# InternetButtonBuzzer.net
KiCad netlist of a schematic drawn in EAGLE
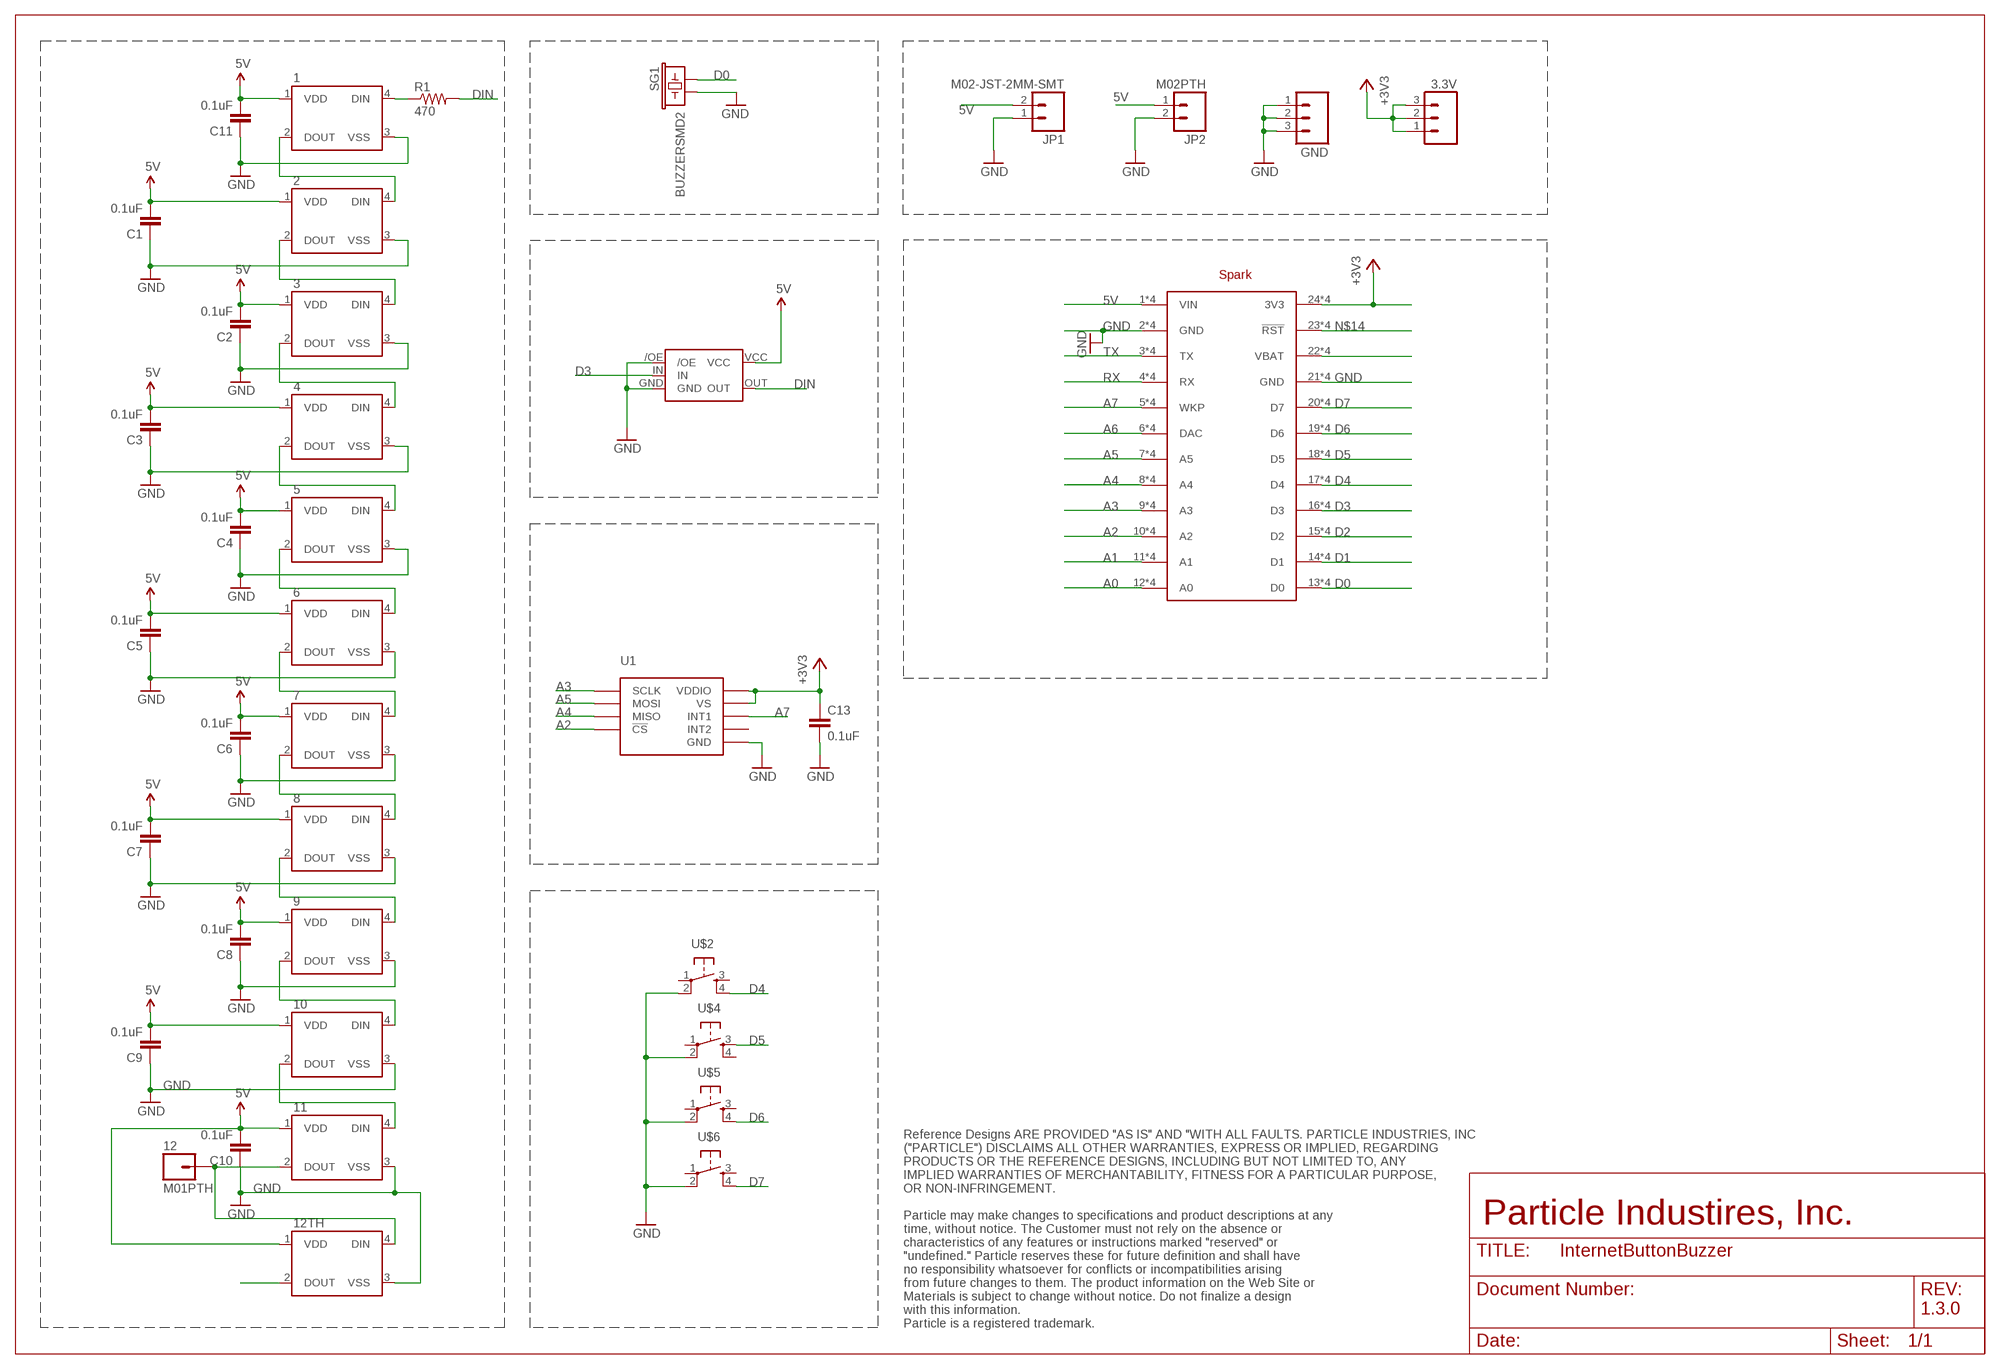
[diagram p0: schematic, sheet 1]

(export (version "E")
  (design (tool "Eeschema 10.0.6"))
  (components
    (comp (ref "1")
      (value "WS2812B")
      (footprint "eagle-import:WS2812B")
      (libsource (lib "eagle-import") (part "SparkFun-LED_WS2812B"))
    )
    (comp (ref "2")
      (value "WS2812B")
      (footprint "eagle-import:WS2812B")
      (libsource (lib "eagle-import") (part "SparkFun-LED_WS2812B"))
    )
    (comp (ref "3")
      (value "WS2812B")
      (footprint "eagle-import:WS2812B")
      (libsource (lib "eagle-import") (part "SparkFun-LED_WS2812B"))
    )
    (comp (ref "3.3V")
      (value "M03LOCK_NO_SILK")
      (footprint "eagle-import:1X03_LOCK_NO_SILK")
      (libsource (lib "eagle-import") (part "M03LOCK_NO_SILK"))
    )
    (comp (ref "4")
      (value "WS2812B")
      (footprint "eagle-import:WS2812B")
      (libsource (lib "eagle-import") (part "SparkFun-LED_WS2812B"))
    )
    (comp (ref "5")
      (value "WS2812B")
      (footprint "eagle-import:WS2812B")
      (libsource (lib "eagle-import") (part "SparkFun-LED_WS2812B"))
    )
    (comp (ref "6")
      (value "WS2812B")
      (footprint "eagle-import:WS2812B")
      (libsource (lib "eagle-import") (part "SparkFun-LED_WS2812B"))
    )
    (comp (ref "7")
      (value "WS2812B")
      (footprint "eagle-import:WS2812B")
      (libsource (lib "eagle-import") (part "SparkFun-LED_WS2812B"))
    )
    (comp (ref "8")
      (value "WS2812B")
      (footprint "eagle-import:WS2812B")
      (libsource (lib "eagle-import") (part "SparkFun-LED_WS2812B"))
    )
    (comp (ref "9")
      (value "WS2812B")
      (footprint "eagle-import:WS2812B")
      (libsource (lib "eagle-import") (part "SparkFun-LED_WS2812B"))
    )
    (comp (ref "10")
      (value "WS2812B")
      (footprint "eagle-import:WS2812B")
      (libsource (lib "eagle-import") (part "SparkFun-LED_WS2812B"))
    )
    (comp (ref "11")
      (value "WS2812B")
      (footprint "eagle-import:WS2812B")
      (libsource (lib "eagle-import") (part "SparkFun-LED_WS2812B"))
    )
    (comp (ref "12")
      (value "M01PTH")
      (footprint "eagle-import:1X01")
      (libsource (lib "eagle-import") (part "M01PTH"))
    )
    (comp (ref "12TH")
      (value "WS2812B")
      (footprint "eagle-import:NOCREAM_WS2812B")
      (libsource (lib "eagle-import") (part "WS2812B"))
    )
    (comp (ref "C1")
      (value "0.1uF")
      (footprint "eagle-import:0603-CAP")
      (libsource (lib "eagle-import") (part "15PF-50V-5%(0603)"))
    )
    (comp (ref "C2")
      (value "0.1uF")
      (footprint "eagle-import:0603-CAP")
      (libsource (lib "eagle-import") (part "15PF-50V-5%(0603)"))
    )
    (comp (ref "C3")
      (value "0.1uF")
      (footprint "eagle-import:0603-CAP")
      (libsource (lib "eagle-import") (part "15PF-50V-5%(0603)"))
    )
    (comp (ref "C4")
      (value "0.1uF")
      (footprint "eagle-import:0603-CAP")
      (libsource (lib "eagle-import") (part "15PF-50V-5%(0603)"))
    )
    (comp (ref "C5")
      (value "0.1uF")
      (footprint "eagle-import:0603-CAP")
      (libsource (lib "eagle-import") (part "15PF-50V-5%(0603)"))
    )
    (comp (ref "C6")
      (value "0.1uF")
      (footprint "eagle-import:0603-CAP")
      (libsource (lib "eagle-import") (part "15PF-50V-5%(0603)"))
    )
    (comp (ref "C7")
      (value "0.1uF")
      (footprint "eagle-import:0603-CAP")
      (libsource (lib "eagle-import") (part "15PF-50V-5%(0603)"))
    )
    (comp (ref "C8")
      (value "0.1uF")
      (footprint "eagle-import:0603-CAP")
      (libsource (lib "eagle-import") (part "15PF-50V-5%(0603)"))
    )
    (comp (ref "C9")
      (value "0.1uF")
      (footprint "eagle-import:0603-CAP")
      (libsource (lib "eagle-import") (part "15PF-50V-5%(0603)"))
    )
    (comp (ref "C10")
      (value "0.1uF")
      (footprint "eagle-import:0603-CAP")
      (libsource (lib "eagle-import") (part "15PF-50V-5%(0603)"))
    )
    (comp (ref "C11")
      (value "0.1uF")
      (footprint "eagle-import:0603-CAP")
      (libsource (lib "eagle-import") (part "15PF-50V-5%(0603)"))
    )
    (comp (ref "C13")
      (value "0.1uF")
      (footprint "eagle-import:0603-CAP")
      (libsource (lib "eagle-import") (part "CAP0603-CAP"))
    )
    (comp (ref "GND")
      (value "M03LOCK_NO_SILK")
      (footprint "eagle-import:1X03_LOCK_NO_SILK")
      (libsource (lib "eagle-import") (part "M03LOCK_NO_SILK"))
    )
    (comp (ref "JP1")
      (value "M02-JST-2MM-SMT")
      (footprint "eagle-import:JST-2-SMD")
      (libsource (lib "eagle-import") (part "M02-JST-2MM-SMT"))
    )
    (comp (ref "JP2")
      (value "M02PTH")
      (footprint "eagle-import:1X02")
      (libsource (lib "eagle-import") (part "M02PTH"))
    )
    (comp (ref "R1")
      (value "470")
      (footprint "eagle-import:0603-RES")
      (libsource (lib "eagle-import") (part "470OHM1/10W1%(0603)"))
    )
    (comp (ref "SG1")
      (value "BUZZERSMD2")
      (footprint "eagle-import:BUZZER-CCV")
      (libsource (lib "eagle-import") (part "BUZZERSMD2"))
    )
    (comp (ref "U$2")
      (value "12MM_TACTILE_SWITCH")
      (footprint "eagle-import:12MM_TACTILE_SWITCH")
      (libsource (lib "eagle-import") (part "12MM_TACTILE_SWITCH"))
    )
    (comp (ref "U$3")
      (value "SPARK_LOGO_WITH_PLANE")
      (footprint "eagle-import:SPARK_LOGO_PLUS_PLANE")
      (libsource (lib "eagle-import") (part "SPARK_LOGO_WITH_PLANE"))
    )
    (comp (ref "U$4")
      (value "12MM_TACTILE_SWITCH")
      (footprint "eagle-import:12MM_TACTILE_SWITCH")
      (libsource (lib "eagle-import") (part "12MM_TACTILE_SWITCH"))
    )
    (comp (ref "U$5")
      (value "12MM_TACTILE_SWITCH")
      (footprint "eagle-import:12MM_TACTILE_SWITCH")
      (libsource (lib "eagle-import") (part "12MM_TACTILE_SWITCH"))
    )
    (comp (ref "U$6")
      (value "12MM_TACTILE_SWITCH")
      (footprint "eagle-import:12MM_TACTILE_SWITCH")
      (libsource (lib "eagle-import") (part "12MM_TACTILE_SWITCH"))
    )
    (comp (ref "U$7")
      (value "SPARK_COREDUAL_HEADER")
      (footprint "eagle-import:SPARK_CORE_DUAL_HEADER")
      (libsource (lib "eagle-import") (part "SPARK_COREDUAL_HEADER"))
    )
    (comp (ref "U$8")
      (value "NL17SZ125SOT553")
      (footprint "eagle-import:SOT-553")
      (libsource (lib "eagle-import") (part "NL17SZ125SOT553"))
    )
    (comp (ref "U1")
      (value "ADXL362ADXL362-1:1")
      (footprint "eagle-import:ADXL362-1_1")
      (libsource (lib "eagle-import") (part "ADXL362ADXL362-1{colon}1"))
    )
  )
  (nets
    (net (code "1") (name "+3V3") (class "Default")
      (node (ref "3.3V") (pin "1") (pinfunction "1_1") (pintype "passive"))
      (node (ref "3.3V") (pin "2") (pinfunction "2_2") (pintype "passive"))
      (node (ref "3.3V") (pin "3") (pinfunction "3_3") (pintype "passive"))
      (node (ref "C13") (pin "1") (pinfunction "1_1") (pintype "passive"))
      (node (ref "U$7") (pin "24") (pinfunction "3V3_24") (pintype "power_in"))
      (node (ref "U$7") (pin "24B") (pinfunction "3V3_24B") (pintype "power_in"))
      (node (ref "U$7") (pin "@24") (pinfunction "3V3_@24") (pintype "power_in"))
      (node (ref "U$7") (pin "@24B") (pinfunction "3V3_@24B") (pintype "power_in"))
      (node (ref "U1") (pin "P$1") (pinfunction "VDDIO_P$1") (pintype "bidirectional"))
      (node (ref "U1") (pin "P$14") (pinfunction "VS_P$14") (pintype "bidirectional"))
    )
    (net (code "2") (name "/A0") (class "Default")
      (node (ref "U$7") (pin "12") (pinfunction "A0_12") (pintype "bidirectional"))
      (node (ref "U$7") (pin "12B") (pinfunction "A0_12B") (pintype "bidirectional"))
      (node (ref "U$7") (pin "@12") (pinfunction "A0_@12") (pintype "bidirectional"))
      (node (ref "U$7") (pin "@12B") (pinfunction "A0_@12B") (pintype "bidirectional"))
    )
    (net (code "3") (name "/A1") (class "Default")
      (node (ref "U$7") (pin "11") (pinfunction "A1_11") (pintype "bidirectional"))
      (node (ref "U$7") (pin "11B") (pinfunction "A1_11B") (pintype "bidirectional"))
      (node (ref "U$7") (pin "@11") (pinfunction "A1_@11") (pintype "bidirectional"))
      (node (ref "U$7") (pin "@11B") (pinfunction "A1_@11B") (pintype "bidirectional"))
    )
    (net (code "4") (name "/A2") (class "Default")
      (node (ref "U$7") (pin "10") (pinfunction "A2_10") (pintype "bidirectional"))
      (node (ref "U$7") (pin "10B") (pinfunction "A2_10B") (pintype "bidirectional"))
      (node (ref "U$7") (pin "@10") (pinfunction "A2_@10") (pintype "bidirectional"))
      (node (ref "U$7") (pin "@10B") (pinfunction "A2_@10B") (pintype "bidirectional"))
      (node (ref "U1") (pin "P$8") (pinfunction "~{CS}_P$8") (pintype "bidirectional"))
    )
    (net (code "5") (name "/A3") (class "Default")
      (node (ref "U$7") (pin "9") (pinfunction "A3_9") (pintype "bidirectional"))
      (node (ref "U$7") (pin "9B") (pinfunction "A3_9B") (pintype "bidirectional"))
      (node (ref "U$7") (pin "@9") (pinfunction "A3_@9") (pintype "bidirectional"))
      (node (ref "U$7") (pin "@9B") (pinfunction "A3_@9B") (pintype "bidirectional"))
      (node (ref "U1") (pin "P$4") (pinfunction "SCLK_P$4") (pintype "bidirectional"))
    )
    (net (code "6") (name "/A4") (class "Default")
      (node (ref "U$7") (pin "8") (pinfunction "A4_8") (pintype "bidirectional"))
      (node (ref "U$7") (pin "8B") (pinfunction "A4_8B") (pintype "bidirectional"))
      (node (ref "U$7") (pin "@8") (pinfunction "A4_@8") (pintype "bidirectional"))
      (node (ref "U$7") (pin "@8B") (pinfunction "A4_@8B") (pintype "bidirectional"))
      (node (ref "U1") (pin "P$7") (pinfunction "MISO_P$7") (pintype "bidirectional"))
    )
    (net (code "7") (name "/A5") (class "Default")
      (node (ref "U$7") (pin "7") (pinfunction "A5_7") (pintype "bidirectional"))
      (node (ref "U$7") (pin "7B") (pinfunction "A5_7B") (pintype "bidirectional"))
      (node (ref "U$7") (pin "@7") (pinfunction "A5_@7") (pintype "bidirectional"))
      (node (ref "U$7") (pin "@7B") (pinfunction "A5_@7B") (pintype "bidirectional"))
      (node (ref "U1") (pin "P$6") (pinfunction "MOSI_P$6") (pintype "bidirectional"))
    )
    (net (code "8") (name "/A6") (class "Default")
      (node (ref "U$7") (pin "6") (pinfunction "DAC_6") (pintype "bidirectional"))
      (node (ref "U$7") (pin "6B") (pinfunction "DAC_6B") (pintype "bidirectional"))
      (node (ref "U$7") (pin "@6") (pinfunction "DAC_@6") (pintype "bidirectional"))
      (node (ref "U$7") (pin "@6B") (pinfunction "DAC_@6B") (pintype "bidirectional"))
    )
    (net (code "9") (name "/A7") (class "Default")
      (node (ref "U$7") (pin "5") (pinfunction "WKP_5") (pintype "bidirectional"))
      (node (ref "U$7") (pin "5B") (pinfunction "WKP_5B") (pintype "bidirectional"))
      (node (ref "U$7") (pin "@5") (pinfunction "WKP_@5") (pintype "bidirectional"))
      (node (ref "U$7") (pin "@5B") (pinfunction "WKP_@5B") (pintype "bidirectional"))
      (node (ref "U1") (pin "P$11") (pinfunction "INT1_P$11") (pintype "bidirectional"))
    )
    (net (code "10") (name "/D0") (class "Default")
      (node (ref "SG1") (pin "+") (pinfunction "1_+") (pintype "passive"))
      (node (ref "U$7") (pin "13") (pinfunction "D0_13") (pintype "bidirectional"))
      (node (ref "U$7") (pin "13B") (pinfunction "D0_13B") (pintype "bidirectional"))
      (node (ref "U$7") (pin "@13") (pinfunction "D0_@13") (pintype "bidirectional"))
      (node (ref "U$7") (pin "@13B") (pinfunction "D0_@13B") (pintype "bidirectional"))
    )
    (net (code "11") (name "/D1") (class "Default")
      (node (ref "U$7") (pin "14") (pinfunction "D1_14") (pintype "bidirectional"))
      (node (ref "U$7") (pin "14B") (pinfunction "D1_14B") (pintype "bidirectional"))
      (node (ref "U$7") (pin "@14") (pinfunction "D1_@14") (pintype "bidirectional"))
      (node (ref "U$7") (pin "@14B") (pinfunction "D1_@14B") (pintype "bidirectional"))
    )
    (net (code "12") (name "/D2") (class "Default")
      (node (ref "U$7") (pin "15") (pinfunction "D2_15") (pintype "bidirectional"))
      (node (ref "U$7") (pin "15B") (pinfunction "D2_15B") (pintype "bidirectional"))
      (node (ref "U$7") (pin "@15") (pinfunction "D2_@15") (pintype "bidirectional"))
      (node (ref "U$7") (pin "@15B") (pinfunction "D2_@15B") (pintype "bidirectional"))
    )
    (net (code "13") (name "/D3") (class "Default")
      (node (ref "U$7") (pin "16") (pinfunction "D3_16") (pintype "bidirectional"))
      (node (ref "U$7") (pin "16B") (pinfunction "D3_16B") (pintype "bidirectional"))
      (node (ref "U$7") (pin "@16") (pinfunction "D3_@16") (pintype "bidirectional"))
      (node (ref "U$7") (pin "@16B") (pinfunction "D3_@16B") (pintype "bidirectional"))
      (node (ref "U$8") (pin "IN") (pinfunction "IN_IN") (pintype "bidirectional"))
    )
    (net (code "14") (name "/D4") (class "Default")
      (node (ref "U$2") (pin "4") (pinfunction "4_4") (pintype "passive"))
      (node (ref "U$7") (pin "17") (pinfunction "D4_17") (pintype "bidirectional"))
      (node (ref "U$7") (pin "17B") (pinfunction "D4_17B") (pintype "bidirectional"))
      (node (ref "U$7") (pin "@17") (pinfunction "D4_@17") (pintype "bidirectional"))
      (node (ref "U$7") (pin "@17B") (pinfunction "D4_@17B") (pintype "bidirectional"))
    )
    (net (code "15") (name "/D5") (class "Default")
      (node (ref "U$4") (pin "3") (pinfunction "3_3") (pintype "passive"))
      (node (ref "U$7") (pin "18") (pinfunction "D5_18") (pintype "bidirectional"))
      (node (ref "U$7") (pin "18B") (pinfunction "D5_18B") (pintype "bidirectional"))
      (node (ref "U$7") (pin "@18") (pinfunction "D5_@18") (pintype "bidirectional"))
      (node (ref "U$7") (pin "@18B") (pinfunction "D5_@18B") (pintype "bidirectional"))
    )
    (net (code "16") (name "/D6") (class "Default")
      (node (ref "U$5") (pin "4") (pinfunction "4_4") (pintype "passive"))
      (node (ref "U$7") (pin "19") (pinfunction "D6_19") (pintype "bidirectional"))
      (node (ref "U$7") (pin "19B") (pinfunction "D6_19B") (pintype "bidirectional"))
      (node (ref "U$7") (pin "@19") (pinfunction "D6_@19") (pintype "bidirectional"))
      (node (ref "U$7") (pin "@19B") (pinfunction "D6_@19B") (pintype "bidirectional"))
    )
    (net (code "17") (name "/D7") (class "Default")
      (node (ref "U$6") (pin "4") (pinfunction "4_4") (pintype "passive"))
      (node (ref "U$7") (pin "20") (pinfunction "D7_20") (pintype "bidirectional"))
      (node (ref "U$7") (pin "20B") (pinfunction "D7_20B") (pintype "bidirectional"))
      (node (ref "U$7") (pin "@20") (pinfunction "D7_@20") (pintype "bidirectional"))
      (node (ref "U$7") (pin "@20B") (pinfunction "D7_@20B") (pintype "bidirectional"))
    )
    (net (code "18") (name "/DIN") (class "Default")
      (node (ref "R1") (pin "2") (pinfunction "2_2") (pintype "passive"))
      (node (ref "U$8") (pin "OUT") (pinfunction "OUT_OUT") (pintype "bidirectional"))
    )
    (net (code "19") (name "/N$14") (class "Default")
      (node (ref "U$7") (pin "23") (pinfunction "~{RST}_23") (pintype "bidirectional"))
      (node (ref "U$7") (pin "23B") (pinfunction "~{RST}_23B") (pintype "bidirectional"))
      (node (ref "U$7") (pin "@23") (pinfunction "~{RST}_@23") (pintype "bidirectional"))
      (node (ref "U$7") (pin "@23B") (pinfunction "~{RST}_@23B") (pintype "bidirectional"))
    )
    (net (code "20") (name "/RX") (class "Default")
      (node (ref "U$7") (pin "4") (pinfunction "RX_4") (pintype "bidirectional"))
      (node (ref "U$7") (pin "4B") (pinfunction "RX_4B") (pintype "bidirectional"))
      (node (ref "U$7") (pin "@4") (pinfunction "RX_@4") (pintype "bidirectional"))
      (node (ref "U$7") (pin "@4B") (pinfunction "RX_@4B") (pintype "bidirectional"))
    )
    (net (code "21") (name "/TX") (class "Default")
      (node (ref "U$7") (pin "3") (pinfunction "TX_3") (pintype "bidirectional"))
      (node (ref "U$7") (pin "3B") (pinfunction "TX_3B") (pintype "bidirectional"))
      (node (ref "U$7") (pin "@3") (pinfunction "TX_@3") (pintype "bidirectional"))
      (node (ref "U$7") (pin "@3B") (pinfunction "TX_@3B") (pintype "bidirectional"))
    )
    (net (code "22") (name "5V") (class "Default")
      (node (ref "1") (pin "1") (pinfunction "VDD_1") (pintype "power_in"))
      (node (ref "10") (pin "1") (pinfunction "VDD_1") (pintype "power_in"))
      (node (ref "11") (pin "1") (pinfunction "VDD_1") (pintype "power_in"))
      (node (ref "12TH") (pin "1") (pinfunction "VDD_1") (pintype "power_in"))
      (node (ref "2") (pin "1") (pinfunction "VDD_1") (pintype "power_in"))
      (node (ref "3") (pin "1") (pinfunction "VDD_1") (pintype "power_in"))
      (node (ref "4") (pin "1") (pinfunction "VDD_1") (pintype "power_in"))
      (node (ref "5") (pin "1") (pinfunction "VDD_1") (pintype "power_in"))
      (node (ref "6") (pin "1") (pinfunction "VDD_1") (pintype "power_in"))
      (node (ref "7") (pin "1") (pinfunction "VDD_1") (pintype "power_in"))
      (node (ref "8") (pin "1") (pinfunction "VDD_1") (pintype "power_in"))
      (node (ref "9") (pin "1") (pinfunction "VDD_1") (pintype "power_in"))
      (node (ref "C1") (pin "2") (pinfunction "2_2") (pintype "passive"))
      (node (ref "C10") (pin "2") (pinfunction "2_2") (pintype "passive"))
      (node (ref "C11") (pin "2") (pinfunction "2_2") (pintype "passive"))
      (node (ref "C2") (pin "2") (pinfunction "2_2") (pintype "passive"))
      (node (ref "C3") (pin "2") (pinfunction "2_2") (pintype "passive"))
      (node (ref "C4") (pin "2") (pinfunction "2_2") (pintype "passive"))
      (node (ref "C5") (pin "2") (pinfunction "2_2") (pintype "passive"))
      (node (ref "C6") (pin "2") (pinfunction "2_2") (pintype "passive"))
      (node (ref "C7") (pin "2") (pinfunction "2_2") (pintype "passive"))
      (node (ref "C8") (pin "2") (pinfunction "2_2") (pintype "passive"))
      (node (ref "C9") (pin "2") (pinfunction "2_2") (pintype "passive"))
      (node (ref "JP1") (pin "2") (pinfunction "1_2") (pintype "passive"))
      (node (ref "JP2") (pin "1") (pinfunction "1_1") (pintype "passive"))
      (node (ref "U$7") (pin "1") (pinfunction "VIN_1") (pintype "power_in"))
      (node (ref "U$7") (pin "1B") (pinfunction "VIN_1B") (pintype "power_in"))
      (node (ref "U$7") (pin "@1") (pinfunction "VIN_@1") (pintype "power_in"))
      (node (ref "U$7") (pin "@1B") (pinfunction "VIN_@1B") (pintype "power_in"))
      (node (ref "U$8") (pin "VCC") (pinfunction "VCC_VCC") (pintype "bidirectional"))
    )
    (net (code "23") (name "GND") (class "Default")
      (node (ref "1") (pin "3") (pinfunction "VSS_3") (pintype "power_in"))
      (node (ref "10") (pin "3") (pinfunction "VSS_3") (pintype "power_in"))
      (node (ref "11") (pin "3") (pinfunction "VSS_3") (pintype "power_in"))
      (node (ref "12TH") (pin "3") (pinfunction "VSS_3") (pintype "power_in"))
      (node (ref "2") (pin "3") (pinfunction "VSS_3") (pintype "power_in"))
      (node (ref "3") (pin "3") (pinfunction "VSS_3") (pintype "power_in"))
      (node (ref "4") (pin "3") (pinfunction "VSS_3") (pintype "power_in"))
      (node (ref "5") (pin "3") (pinfunction "VSS_3") (pintype "power_in"))
      (node (ref "6") (pin "3") (pinfunction "VSS_3") (pintype "power_in"))
      (node (ref "7") (pin "3") (pinfunction "VSS_3") (pintype "power_in"))
      (node (ref "8") (pin "3") (pinfunction "VSS_3") (pintype "power_in"))
      (node (ref "9") (pin "3") (pinfunction "VSS_3") (pintype "power_in"))
      (node (ref "C1") (pin "1") (pinfunction "1_1") (pintype "passive"))
      (node (ref "C10") (pin "1") (pinfunction "1_1") (pintype "passive"))
      (node (ref "C11") (pin "1") (pinfunction "1_1") (pintype "passive"))
      (node (ref "C13") (pin "2") (pinfunction "2_2") (pintype "passive"))
      (node (ref "C2") (pin "1") (pinfunction "1_1") (pintype "passive"))
      (node (ref "C3") (pin "1") (pinfunction "1_1") (pintype "passive"))
      (node (ref "C4") (pin "1") (pinfunction "1_1") (pintype "passive"))
      (node (ref "C5") (pin "1") (pinfunction "1_1") (pintype "passive"))
      (node (ref "C6") (pin "1") (pinfunction "1_1") (pintype "passive"))
      (node (ref "C7") (pin "1") (pinfunction "1_1") (pintype "passive"))
      (node (ref "C8") (pin "1") (pinfunction "1_1") (pintype "passive"))
      (node (ref "C9") (pin "1") (pinfunction "1_1") (pintype "passive"))
      (node (ref "GND") (pin "1") (pinfunction "1_1") (pintype "passive"))
      (node (ref "GND") (pin "2") (pinfunction "2_2") (pintype "passive"))
      (node (ref "GND") (pin "3") (pinfunction "3_3") (pintype "passive"))
      (node (ref "JP1") (pin "1") (pinfunction "2_1") (pintype "passive"))
      (node (ref "JP2") (pin "2") (pinfunction "2_2") (pintype "passive"))
      (node (ref "SG1") (pin "-") (pinfunction "2_-") (pintype "passive"))
      (node (ref "U$2") (pin "2") (pinfunction "2_2") (pintype "passive"))
      (node (ref "U$4") (pin "2") (pinfunction "2_2") (pintype "passive"))
      (node (ref "U$5") (pin "2") (pinfunction "2_2") (pintype "passive"))
      (node (ref "U$6") (pin "2") (pinfunction "2_2") (pintype "passive"))
      (node (ref "U$7") (pin "2") (pinfunction "GND_2") (pintype "power_in"))
      (node (ref "U$7") (pin "21") (pinfunction "GND_21") (pintype "power_in"))
      (node (ref "U$7") (pin "21B") (pinfunction "GND_21B") (pintype "power_in"))
      (node (ref "U$7") (pin "2B") (pinfunction "GND_2B") (pintype "power_in"))
      (node (ref "U$7") (pin "@2") (pinfunction "GND_@2") (pintype "power_in"))
      (node (ref "U$7") (pin "@21") (pinfunction "GND_@21") (pintype "power_in"))
      (node (ref "U$7") (pin "@21B") (pinfunction "GND_@21B") (pintype "power_in"))
      (node (ref "U$7") (pin "@2B") (pinfunction "GND_@2B") (pintype "power_in"))
      (node (ref "U$8") (pin "/OE") (pinfunction "/OE_/OE") (pintype "bidirectional"))
      (node (ref "U$8") (pin "GND") (pinfunction "GND_GND") (pintype "bidirectional"))
      (node (ref "U1") (pin "P$12") (pinfunction "GND_P$12") (pintype "bidirectional"))
      (node (ref "U1") (pin "P$13") (pinfunction "GND_P$13") (pintype "bidirectional"))
      (node (ref "U1") (pin "P$16") (pinfunction "GND_P$16") (pintype "bidirectional"))
    )
    (net (code "24") (name "Net-(1-DIN)") (class "Default")
      (node (ref "1") (pin "4") (pinfunction "DIN_4") (pintype "input"))
      (node (ref "R1") (pin "1") (pinfunction "1_1") (pintype "passive"))
    )
    (net (code "25") (name "Net-(1-DOUT)") (class "Default")
      (node (ref "1") (pin "2") (pinfunction "DOUT_2") (pintype "output"))
      (node (ref "2") (pin "4") (pinfunction "DIN_4") (pintype "input"))
    )
    (net (code "26") (name "Net-(2-DOUT)") (class "Default")
      (node (ref "2") (pin "2") (pinfunction "DOUT_2") (pintype "output"))
      (node (ref "3") (pin "4") (pinfunction "DIN_4") (pintype "input"))
    )
    (net (code "27") (name "Net-(3-DOUT)") (class "Default")
      (node (ref "3") (pin "2") (pinfunction "DOUT_2") (pintype "output"))
      (node (ref "4") (pin "4") (pinfunction "DIN_4") (pintype "input"))
    )
    (net (code "28") (name "Net-(4-DOUT)") (class "Default")
      (node (ref "4") (pin "2") (pinfunction "DOUT_2") (pintype "output"))
      (node (ref "5") (pin "4") (pinfunction "DIN_4") (pintype "input"))
    )
    (net (code "29") (name "Net-(5-DOUT)") (class "Default")
      (node (ref "5") (pin "2") (pinfunction "DOUT_2") (pintype "output"))
      (node (ref "6") (pin "4") (pinfunction "DIN_4") (pintype "input"))
    )
    (net (code "30") (name "Net-(6-DOUT)") (class "Default")
      (node (ref "6") (pin "2") (pinfunction "DOUT_2") (pintype "output"))
      (node (ref "7") (pin "4") (pinfunction "DIN_4") (pintype "input"))
    )
    (net (code "31") (name "Net-(7-DOUT)") (class "Default")
      (node (ref "7") (pin "2") (pinfunction "DOUT_2") (pintype "output"))
      (node (ref "8") (pin "4") (pinfunction "DIN_4") (pintype "input"))
    )
    (net (code "32") (name "Net-(8-DOUT)") (class "Default")
      (node (ref "8") (pin "2") (pinfunction "DOUT_2") (pintype "output"))
      (node (ref "9") (pin "4") (pinfunction "DIN_4") (pintype "input"))
    )
    (net (code "33") (name "Net-(10-DIN)") (class "Default")
      (node (ref "10") (pin "4") (pinfunction "DIN_4") (pintype "input"))
      (node (ref "9") (pin "2") (pinfunction "DOUT_2") (pintype "output"))
    )
    (net (code "34") (name "Net-(10-DOUT)") (class "Default")
      (node (ref "10") (pin "2") (pinfunction "DOUT_2") (pintype "output"))
      (node (ref "11") (pin "4") (pinfunction "DIN_4") (pintype "input"))
    )
    (net (code "35") (name "Net-(11-DOUT)") (class "Default")
      (node (ref "11") (pin "2") (pinfunction "DOUT_2") (pintype "output"))
      (node (ref "12") (pin "1") (pinfunction "1_1") (pintype "passive"))
      (node (ref "12TH") (pin "4") (pinfunction "DIN_4") (pintype "input"))
    )
    (net (code "36") (name "Net-(U$7-VBAT-Pad22)") (class "Default")
      (node (ref "U$7") (pin "22") (pinfunction "VBAT_22") (pintype "power_in"))
      (node (ref "U$7") (pin "22B") (pinfunction "VBAT_22B") (pintype "power_in"))
      (node (ref "U$7") (pin "@22") (pinfunction "VBAT_@22") (pintype "power_in"))
      (node (ref "U$7") (pin "@22B") (pinfunction "VBAT_@22B") (pintype "power_in"))
    )
    (net (code "37") (name "unconnected-(12TH-DOUT-Pad2)") (class "Default")
      (node (ref "12TH") (pin "2") (pinfunction "DOUT_2") (pintype "output"))
    )
    (net (code "38") (name "unconnected-(U$2-Pad1)") (class "Default")
      (node (ref "U$2") (pin "1") (pinfunction "1_1") (pintype "passive"))
    )
    (net (code "39") (name "unconnected-(U$2-Pad3)") (class "Default")
      (node (ref "U$2") (pin "3") (pinfunction "3_3") (pintype "passive"))
    )
    (net (code "40") (name "unconnected-(U$4-Pad1)") (class "Default")
      (node (ref "U$4") (pin "1") (pinfunction "1_1") (pintype "passive"))
    )
    (net (code "41") (name "unconnected-(U$4-Pad4)") (class "Default")
      (node (ref "U$4") (pin "4") (pinfunction "4_4") (pintype "passive"))
    )
    (net (code "42") (name "unconnected-(U$5-Pad1)") (class "Default")
      (node (ref "U$5") (pin "1") (pinfunction "1_1") (pintype "passive"))
    )
    (net (code "43") (name "unconnected-(U$5-Pad3)") (class "Default")
      (node (ref "U$5") (pin "3") (pinfunction "3_3") (pintype "passive"))
    )
    (net (code "44") (name "unconnected-(U$6-Pad1)") (class "Default")
      (node (ref "U$6") (pin "1") (pinfunction "1_1") (pintype "passive"))
    )
    (net (code "45") (name "unconnected-(U$6-Pad3)") (class "Default")
      (node (ref "U$6") (pin "3") (pinfunction "3_3") (pintype "passive"))
    )
    (net (code "46") (name "unconnected-(U1-INT2-PadP$9)") (class "Default")
      (node (ref "U1") (pin "P$9") (pinfunction "INT2_P$9") (pintype "bidirectional"))
    )
  )
)
